# pnode.net
KiCad netlist of a schematic drawn in EAGLE
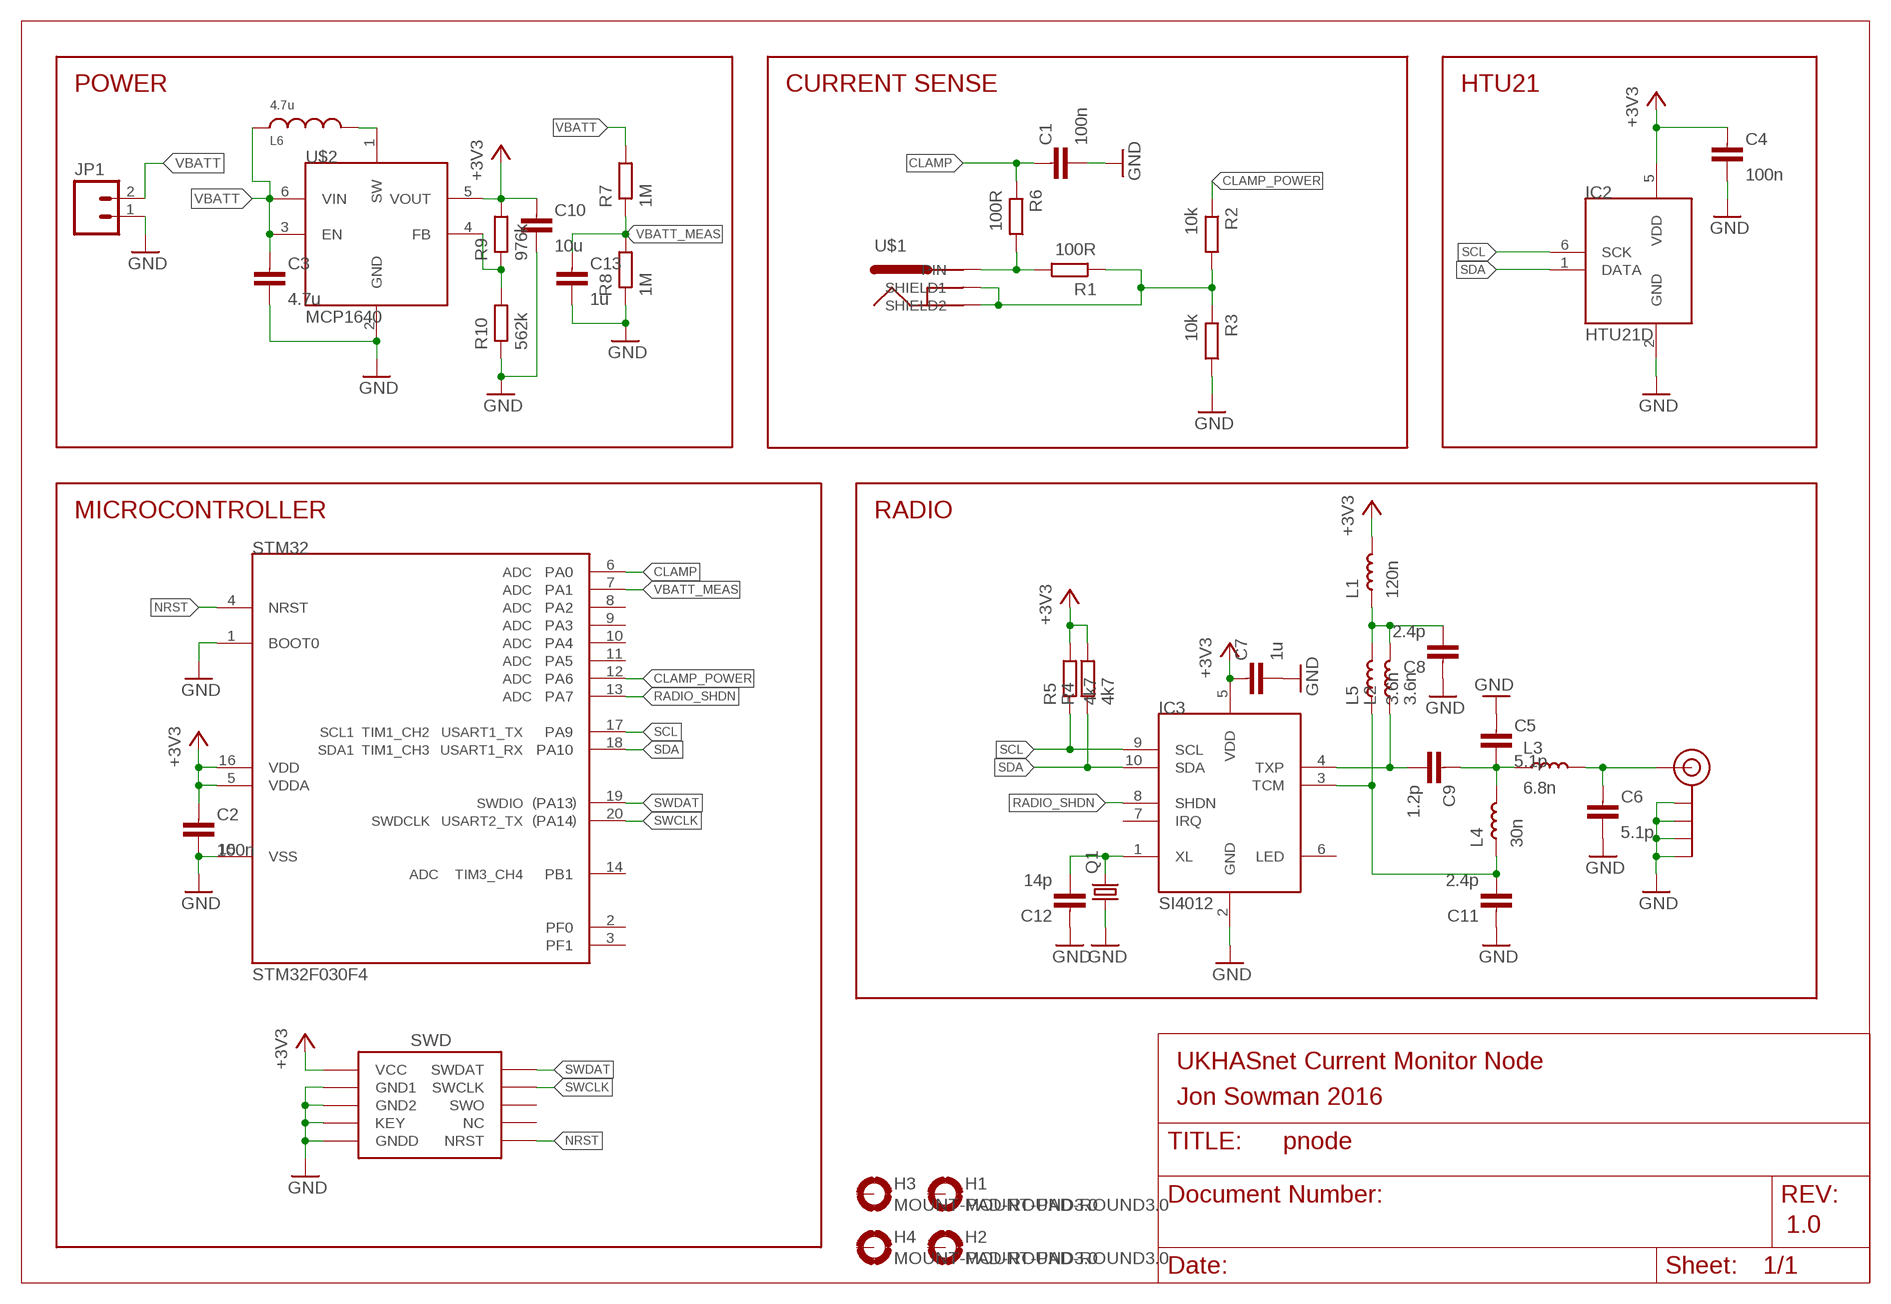
[diagram p0: schematic, sheet 1]

(export (version "E")
  (design (tool "Eeschema 10.0.6"))
  (components
    (comp (ref "C1")
      (value "100n")
      (footprint "eagle-import:C0603-N")
      (libsource (lib "eagle-import") (part "CAPACITOR0603-N"))
    )
    (comp (ref "C2")
      (value "100n")
      (footprint "eagle-import:C0603-N")
      (libsource (lib "eagle-import") (part "CAPACITOR0603-N"))
    )
    (comp (ref "C3")
      (value "4.7u")
      (footprint "eagle-import:C0603-N")
      (libsource (lib "eagle-import") (part "CAPACITOR0603-N"))
    )
    (comp (ref "C4")
      (value "100n")
      (footprint "eagle-import:C0603-N")
      (libsource (lib "eagle-import") (part "CAPACITOR0603-N"))
    )
    (comp (ref "C5")
      (value "5.1p")
      (footprint "eagle-import:C0603-N")
      (libsource (lib "eagle-import") (part "CAPACITOR0603-N"))
    )
    (comp (ref "C6")
      (value "5.1p")
      (footprint "eagle-import:C0603-N")
      (libsource (lib "eagle-import") (part "CAPACITOR0603-N"))
    )
    (comp (ref "C7")
      (value "1u")
      (footprint "eagle-import:C0603-N")
      (libsource (lib "eagle-import") (part "CAPACITOR0603-N"))
    )
    (comp (ref "C8")
      (value "2.4p")
      (footprint "eagle-import:C0603-N")
      (libsource (lib "eagle-import") (part "CAPACITOR0603-N"))
    )
    (comp (ref "C9")
      (value "1.2p")
      (footprint "eagle-import:C0603-N")
      (libsource (lib "eagle-import") (part "CAPACITOR0603-N"))
    )
    (comp (ref "C10")
      (value "10u")
      (footprint "eagle-import:C0603-N")
      (libsource (lib "eagle-import") (part "CAPACITOR0603-N"))
    )
    (comp (ref "C11")
      (value "2.4p")
      (footprint "eagle-import:C0603-N")
      (libsource (lib "eagle-import") (part "CAPACITOR0603-N"))
    )
    (comp (ref "C12")
      (value "14p")
      (footprint "eagle-import:C0603-N")
      (libsource (lib "eagle-import") (part "CAPACITOR0603-N"))
    )
    (comp (ref "C13")
      (value "1u")
      (footprint "eagle-import:C0603-N")
      (libsource (lib "eagle-import") (part "CAPACITOR0603-N"))
    )
    (comp (ref "H1")
      (value "MOUNT-PAD-ROUND3.0")
      (footprint "eagle-import:3,0-PAD")
      (libsource (lib "eagle-import") (part "MOUNT-PAD-ROUND3.0"))
    )
    (comp (ref "H2")
      (value "MOUNT-PAD-ROUND3.0")
      (footprint "eagle-import:3,0-PAD")
      (libsource (lib "eagle-import") (part "MOUNT-PAD-ROUND3.0"))
    )
    (comp (ref "H3")
      (value "MOUNT-PAD-ROUND3.0")
      (footprint "eagle-import:3,0-PAD")
      (libsource (lib "eagle-import") (part "MOUNT-PAD-ROUND3.0"))
    )
    (comp (ref "H4")
      (value "MOUNT-PAD-ROUND3.0")
      (footprint "eagle-import:3,0-PAD")
      (libsource (lib "eagle-import") (part "MOUNT-PAD-ROUND3.0"))
    )
    (comp (ref "IC2")
      (value "HTU21D")
      (footprint "eagle-import:DFN6-L")
      (libsource (lib "eagle-import") (part "HTU21D"))
    )
    (comp (ref "IC3")
      (value "SI4012")
      (footprint "eagle-import:MSOP10")
      (libsource (lib "eagle-import") (part "SI4012"))
    )
    (comp (ref "J$1")
      (value "SMA_EDGE")
      (footprint "eagle-import:SMA-EDGE")
      (libsource (lib "eagle-import") (part "SMA_EDGE"))
    )
    (comp (ref "J1")
      (value "SWD_SHROUD_SMD")
      (footprint "eagle-import:SWD_SMD_SHROUD")
      (libsource (lib "eagle-import") (part "SWD_SHROUD_SMD"))
    )
    (comp (ref "JP1")
      (value "M02PTH")
      (footprint "eagle-import:1X02")
      (libsource (lib "eagle-import") (part "M02PTH"))
    )
    (comp (ref "L1")
      (value "120n")
      (footprint "eagle-import:L0603-N")
      (libsource (lib "eagle-import") (part "INDUCTOR0603-N"))
    )
    (comp (ref "L2")
      (value "3.6n")
      (footprint "eagle-import:L0402-N")
      (libsource (lib "eagle-import") (part "INDUCTOR0402-N"))
    )
    (comp (ref "L3")
      (value "6.8n")
      (footprint "eagle-import:L0402-N")
      (libsource (lib "eagle-import") (part "INDUCTOR0402-N"))
    )
    (comp (ref "L4")
      (value "30n")
      (footprint "eagle-import:L0402-N")
      (libsource (lib "eagle-import") (part "INDUCTOR0402-N"))
    )
    (comp (ref "L5")
      (value "3.6n")
      (footprint "eagle-import:L0402-N")
      (libsource (lib "eagle-import") (part "INDUCTOR0402-N"))
    )
    (comp (ref "L6")
      (value "4.7u")
      (footprint "eagle-import:BOURNS_SDE0403A")
      (libsource (lib "eagle-import") (part "BOURNS_SDE0403A"))
    )
    (comp (ref "Q1")
      (value "CRYSTALHC49S")
      (footprint "eagle-import:HC49_S")
      (libsource (lib "eagle-import") (part "CRYSTALHC49S"))
    )
    (comp (ref "R1")
      (value "100R")
      (footprint "eagle-import:R0603-N")
      (libsource (lib "eagle-import") (part "RESISTOR0603-N"))
    )
    (comp (ref "R2")
      (value "10k")
      (footprint "eagle-import:R0603-N")
      (libsource (lib "eagle-import") (part "RESISTOR0603-N"))
    )
    (comp (ref "R3")
      (value "10k")
      (footprint "eagle-import:R0603-N")
      (libsource (lib "eagle-import") (part "RESISTOR0603-N"))
    )
    (comp (ref "R4")
      (value "4k7")
      (footprint "eagle-import:R0603-N")
      (libsource (lib "eagle-import") (part "RESISTOR0603-N"))
    )
    (comp (ref "R5")
      (value "4k7")
      (footprint "eagle-import:R0603-N")
      (libsource (lib "eagle-import") (part "RESISTOR0603-N"))
    )
    (comp (ref "R6")
      (value "100R")
      (footprint "eagle-import:R0603-N")
      (libsource (lib "eagle-import") (part "RESISTOR0603-N"))
    )
    (comp (ref "R7")
      (value "1M")
      (footprint "eagle-import:R0603-N")
      (libsource (lib "eagle-import") (part "RESISTOR0603-N"))
    )
    (comp (ref "R8")
      (value "1M")
      (footprint "eagle-import:R0603-N")
      (libsource (lib "eagle-import") (part "RESISTOR0603-N"))
    )
    (comp (ref "R9")
      (value "976k")
      (footprint "eagle-import:R0603-N")
      (libsource (lib "eagle-import") (part "RESISTOR0603-N"))
    )
    (comp (ref "R10")
      (value "562k")
      (footprint "eagle-import:R0603-N")
      (libsource (lib "eagle-import") (part "RESISTOR0603-N"))
    )
    (comp (ref "STM32")
      (value "STM32F030F4")
      (footprint "eagle-import:TSSOP20")
      (libsource (lib "eagle-import") (part "STM32F030F4"))
    )
    (comp (ref "U$1")
      (value "13MM_DC_JACKPTH")
      (footprint "eagle-import:13MM_DC_JACK")
      (libsource (lib "eagle-import") (part "13MM_DC_JACKPTH"))
    )
    (comp (ref "U$2")
      (value "MCP1640")
      (footprint "eagle-import:SOT23-6")
      (libsource (lib "eagle-import") (part "MCP1640"))
    )
  )
  (nets
    (net (code "1") (name "+3V3") (class "Default")
      (node (ref "C10") (pin "1") (pinfunction "1_1") (pintype "passive"))
      (node (ref "C2") (pin "1") (pinfunction "1_1") (pintype "passive"))
      (node (ref "C4") (pin "1") (pinfunction "1_1") (pintype "passive"))
      (node (ref "C7") (pin "1") (pinfunction "1_1") (pintype "passive"))
      (node (ref "IC2") (pin "5") (pinfunction "VDD_5") (pintype "power_in"))
      (node (ref "IC3") (pin "5") (pinfunction "VDD_5") (pintype "power_in"))
      (node (ref "J1") (pin "1") (pinfunction "VCC_1") (pintype "power_in"))
      (node (ref "L1") (pin "2") (pinfunction "P$2_2") (pintype "passive"))
      (node (ref "R4") (pin "2") (pinfunction "P$2_2") (pintype "passive"))
      (node (ref "R5") (pin "2") (pinfunction "P$2_2") (pintype "passive"))
      (node (ref "R9") (pin "2") (pinfunction "P$2_2") (pintype "passive"))
      (node (ref "STM32") (pin "16") (pinfunction "VDD_16") (pintype "power_in"))
      (node (ref "STM32") (pin "5") (pinfunction "VDDA_5") (pintype "power_in"))
      (node (ref "U$2") (pin "5") (pinfunction "VOUT_5") (pintype "output"))
    )
    (net (code "2") (name "CLAMP") (class "Default")
      (node (ref "C1") (pin "1") (pinfunction "1_1") (pintype "passive"))
      (node (ref "R6") (pin "1") (pinfunction "P$1_1") (pintype "passive"))
      (node (ref "STM32") (pin "6") (pinfunction "PA0_6") (pintype "bidirectional"))
    )
    (net (code "3") (name "CLAMP_POWER") (class "Default")
      (node (ref "R2") (pin "1") (pinfunction "P$1_1") (pintype "passive"))
      (node (ref "STM32") (pin "12") (pinfunction "PA6_12") (pintype "bidirectional"))
    )
    (net (code "4") (name "GND") (class "Default")
      (node (ref "C1") (pin "2") (pinfunction "2_2") (pintype "passive"))
      (node (ref "C10") (pin "2") (pinfunction "2_2") (pintype "passive"))
      (node (ref "C11") (pin "1") (pinfunction "1_1") (pintype "passive"))
      (node (ref "C12") (pin "1") (pinfunction "1_1") (pintype "passive"))
      (node (ref "C13") (pin "2") (pinfunction "2_2") (pintype "passive"))
      (node (ref "C2") (pin "2") (pinfunction "2_2") (pintype "passive"))
      (node (ref "C3") (pin "2") (pinfunction "2_2") (pintype "passive"))
      (node (ref "C4") (pin "2") (pinfunction "2_2") (pintype "passive"))
      (node (ref "C5") (pin "1") (pinfunction "1_1") (pintype "passive"))
      (node (ref "C6") (pin "2") (pinfunction "2_2") (pintype "passive"))
      (node (ref "C7") (pin "2") (pinfunction "2_2") (pintype "passive"))
      (node (ref "C8") (pin "1") (pinfunction "1_1") (pintype "passive"))
      (node (ref "IC2") (pin "2") (pinfunction "GND_2") (pintype "power_in"))
      (node (ref "IC3") (pin "2") (pinfunction "GND_2") (pintype "power_in"))
      (node (ref "J$1") (pin "GND@0") (pinfunction "GND_GND@0") (pintype "bidirectional"))
      (node (ref "J$1") (pin "GND@1") (pinfunction "GND_GND@1") (pintype "bidirectional"))
      (node (ref "J$1") (pin "GND@2") (pinfunction "GND_GND@2") (pintype "bidirectional"))
      (node (ref "J$1") (pin "GND@3") (pinfunction "GND_GND@3") (pintype "bidirectional"))
      (node (ref "J1") (pin "3") (pinfunction "GND1_3") (pintype "power_in"))
      (node (ref "J1") (pin "5") (pinfunction "GND2_5") (pintype "power_in"))
      (node (ref "J1") (pin "7") (pinfunction "KEY_7") (pintype "bidirectional"))
      (node (ref "J1") (pin "9") (pinfunction "GNDD_9") (pintype "power_in"))
      (node (ref "JP1") (pin "1") (pinfunction "1_1") (pintype "passive"))
      (node (ref "Q1") (pin "1") (pinfunction "1_1") (pintype "passive"))
      (node (ref "R10") (pin "1") (pinfunction "P$1_1") (pintype "passive"))
      (node (ref "R3") (pin "2") (pinfunction "P$2_2") (pintype "passive"))
      (node (ref "R8") (pin "1") (pinfunction "P$1_1") (pintype "passive"))
      (node (ref "STM32") (pin "1") (pinfunction "BOOT0_1") (pintype "input"))
      (node (ref "STM32") (pin "15") (pinfunction "VSS_15") (pintype "power_in"))
      (node (ref "U$2") (pin "2") (pinfunction "GND_2") (pintype "power_in"))
    )
    (net (code "5") (name "NRST") (class "Default")
      (node (ref "J1") (pin "10") (pinfunction "NRST_10") (pintype "bidirectional"))
      (node (ref "STM32") (pin "4") (pinfunction "NRST_4") (pintype "input"))
    )
    (net (code "6") (name "Net-(IC3-TCM)") (class "Default")
      (node (ref "C11") (pin "2") (pinfunction "2_2") (pintype "passive"))
      (node (ref "IC3") (pin "3") (pinfunction "TCM_3") (pintype "output"))
      (node (ref "L4") (pin "1") (pinfunction "P$1_1") (pintype "passive"))
      (node (ref "L5") (pin "1") (pinfunction "P$1_1") (pintype "passive"))
    )
    (net (code "7") (name "Net-(IC3-TXP)") (class "Default")
      (node (ref "C9") (pin "2") (pinfunction "2_2") (pintype "passive"))
      (node (ref "IC3") (pin "4") (pinfunction "TXP_4") (pintype "output"))
      (node (ref "L2") (pin "1") (pinfunction "P$1_1") (pintype "passive"))
    )
    (net (code "8") (name "Net-(IC3-XL)") (class "Default")
      (node (ref "C12") (pin "2") (pinfunction "2_2") (pintype "passive"))
      (node (ref "IC3") (pin "1") (pinfunction "XL_1") (pintype "bidirectional"))
      (node (ref "Q1") (pin "2") (pinfunction "2_2") (pintype "passive"))
    )
    (net (code "9") (name "Net-(J$1-SIGNAL)") (class "Default")
      (node (ref "C6") (pin "1") (pinfunction "1_1") (pintype "passive"))
      (node (ref "J$1") (pin "SIG") (pinfunction "SIGNAL_SIG") (pintype "bidirectional"))
      (node (ref "L3") (pin "2") (pinfunction "P$2_2") (pintype "passive"))
    )
    (net (code "10") (name "Net-(L1-P$1)") (class "Default")
      (node (ref "C8") (pin "2") (pinfunction "2_2") (pintype "passive"))
      (node (ref "L1") (pin "1") (pinfunction "P$1_1") (pintype "passive"))
      (node (ref "L2") (pin "2") (pinfunction "P$2_2") (pintype "passive"))
      (node (ref "L5") (pin "2") (pinfunction "P$2_2") (pintype "passive"))
    )
    (net (code "11") (name "Net-(L3-P$1)") (class "Default")
      (node (ref "C5") (pin "2") (pinfunction "2_2") (pintype "passive"))
      (node (ref "C9") (pin "1") (pinfunction "1_1") (pintype "passive"))
      (node (ref "L3") (pin "1") (pinfunction "P$1_1") (pintype "passive"))
      (node (ref "L4") (pin "2") (pinfunction "P$2_2") (pintype "passive"))
    )
    (net (code "12") (name "Net-(R1-P$1)") (class "Default")
      (node (ref "R1") (pin "1") (pinfunction "P$1_1") (pintype "passive"))
      (node (ref "R2") (pin "2") (pinfunction "P$2_2") (pintype "passive"))
      (node (ref "R3") (pin "1") (pinfunction "P$1_1") (pintype "passive"))
      (node (ref "U$1") (pin "2") (pinfunction "SHIELD1_2") (pintype "bidirectional"))
      (node (ref "U$1") (pin "3") (pinfunction "SHIELD2_3") (pintype "bidirectional"))
    )
    (net (code "13") (name "Net-(R1-P$2)") (class "Default")
      (node (ref "R1") (pin "2") (pinfunction "P$2_2") (pintype "passive"))
      (node (ref "R6") (pin "2") (pinfunction "P$2_2") (pintype "passive"))
      (node (ref "U$1") (pin "1") (pinfunction "PIN_1") (pintype "bidirectional"))
    )
    (net (code "14") (name "Net-(R10-P$2)") (class "Default")
      (node (ref "R10") (pin "2") (pinfunction "P$2_2") (pintype "passive"))
      (node (ref "R9") (pin "1") (pinfunction "P$1_1") (pintype "passive"))
      (node (ref "U$2") (pin "4") (pinfunction "FB_4") (pintype "input"))
    )
    (net (code "15") (name "Net-(U$2-SW)") (class "Default")
      (node (ref "L6") (pin "P$2") (pinfunction "P$2_P$2") (pintype "bidirectional"))
      (node (ref "U$2") (pin "1") (pinfunction "SW_1") (pintype "input"))
    )
    (net (code "16") (name "RADIO_SHDN") (class "Default")
      (node (ref "IC3") (pin "8") (pinfunction "SHDN_8") (pintype "input"))
      (node (ref "STM32") (pin "13") (pinfunction "PA7_13") (pintype "bidirectional"))
    )
    (net (code "17") (name "SCL") (class "Default")
      (node (ref "IC2") (pin "6") (pinfunction "SCK_6") (pintype "input"))
      (node (ref "IC3") (pin "9") (pinfunction "SCL_9") (pintype "input"))
      (node (ref "R5") (pin "1") (pinfunction "P$1_1") (pintype "passive"))
      (node (ref "STM32") (pin "17") (pinfunction "PA9_17") (pintype "bidirectional"))
    )
    (net (code "18") (name "SDA") (class "Default")
      (node (ref "IC2") (pin "1") (pinfunction "DATA_1") (pintype "bidirectional"))
      (node (ref "IC3") (pin "10") (pinfunction "SDA_10") (pintype "bidirectional"))
      (node (ref "R4") (pin "1") (pinfunction "P$1_1") (pintype "passive"))
      (node (ref "STM32") (pin "18") (pinfunction "PA10_18") (pintype "bidirectional"))
    )
    (net (code "19") (name "SWCLK") (class "Default")
      (node (ref "J1") (pin "4") (pinfunction "SWCLK_4") (pintype "bidirectional"))
      (node (ref "STM32") (pin "20") (pinfunction "PA14_20") (pintype "bidirectional"))
    )
    (net (code "20") (name "SWDAT") (class "Default")
      (node (ref "J1") (pin "2") (pinfunction "SWDAT_2") (pintype "bidirectional"))
      (node (ref "STM32") (pin "19") (pinfunction "PA13_19") (pintype "bidirectional"))
    )
    (net (code "21") (name "VBATT") (class "Default")
      (node (ref "C3") (pin "1") (pinfunction "1_1") (pintype "passive"))
      (node (ref "JP1") (pin "2") (pinfunction "2_2") (pintype "passive"))
      (node (ref "L6") (pin "P$1") (pinfunction "P$1_P$1") (pintype "bidirectional"))
      (node (ref "R7") (pin "2") (pinfunction "P$2_2") (pintype "passive"))
      (node (ref "U$2") (pin "3") (pinfunction "EN_3") (pintype "input"))
      (node (ref "U$2") (pin "6") (pinfunction "VIN_6") (pintype "power_in"))
    )
    (net (code "22") (name "VBATT_MEAS") (class "Default")
      (node (ref "C13") (pin "1") (pinfunction "1_1") (pintype "passive"))
      (node (ref "R7") (pin "1") (pinfunction "P$1_1") (pintype "passive"))
      (node (ref "R8") (pin "2") (pinfunction "P$2_2") (pintype "passive"))
      (node (ref "STM32") (pin "7") (pinfunction "PA1_7") (pintype "bidirectional"))
    )
    (net (code "23") (name "unconnected-(H1-MOUNT-PadB3,0)") (class "Default")
      (node (ref "H1") (pin "B3,0") (pinfunction "MOUNT_B3,0") (pintype "passive"))
    )
    (net (code "24") (name "unconnected-(H2-MOUNT-PadB3,0)") (class "Default")
      (node (ref "H2") (pin "B3,0") (pinfunction "MOUNT_B3,0") (pintype "passive"))
    )
    (net (code "25") (name "unconnected-(H3-MOUNT-PadB3,0)") (class "Default")
      (node (ref "H3") (pin "B3,0") (pinfunction "MOUNT_B3,0") (pintype "passive"))
    )
    (net (code "26") (name "unconnected-(H4-MOUNT-PadB3,0)") (class "Default")
      (node (ref "H4") (pin "B3,0") (pinfunction "MOUNT_B3,0") (pintype "passive"))
    )
    (net (code "27") (name "unconnected-(IC3-IRQ-Pad7)") (class "Default")
      (node (ref "IC3") (pin "7") (pinfunction "IRQ_7") (pintype "output"))
    )
    (net (code "28") (name "unconnected-(IC3-LED-Pad6)") (class "Default")
      (node (ref "IC3") (pin "6") (pinfunction "LED_6") (pintype "output"))
    )
    (net (code "29") (name "unconnected-(J1-NC-Pad8)") (class "Default")
      (node (ref "J1") (pin "8") (pinfunction "NC_8") (pintype "no_connect"))
    )
    (net (code "30") (name "unconnected-(J1-SWO-Pad6)") (class "Default")
      (node (ref "J1") (pin "6") (pinfunction "SWO_6") (pintype "bidirectional"))
    )
    (net (code "31") (name "unconnected-(STM32-PA2-Pad8)") (class "Default")
      (node (ref "STM32") (pin "8") (pinfunction "PA2_8") (pintype "bidirectional"))
    )
    (net (code "32") (name "unconnected-(STM32-PA3-Pad9)") (class "Default")
      (node (ref "STM32") (pin "9") (pinfunction "PA3_9") (pintype "bidirectional"))
    )
    (net (code "33") (name "unconnected-(STM32-PA4-Pad10)") (class "Default")
      (node (ref "STM32") (pin "10") (pinfunction "PA4_10") (pintype "bidirectional"))
    )
    (net (code "34") (name "unconnected-(STM32-PA5-Pad11)") (class "Default")
      (node (ref "STM32") (pin "11") (pinfunction "PA5_11") (pintype "bidirectional"))
    )
    (net (code "35") (name "unconnected-(STM32-PB1-Pad14)") (class "Default")
      (node (ref "STM32") (pin "14") (pinfunction "PB1_14") (pintype "bidirectional"))
    )
    (net (code "36") (name "unconnected-(STM32-PF0-Pad2)") (class "Default")
      (node (ref "STM32") (pin "2") (pinfunction "PF0_2") (pintype "bidirectional"))
    )
    (net (code "37") (name "unconnected-(STM32-PF1-Pad3)") (class "Default")
      (node (ref "STM32") (pin "3") (pinfunction "PF1_3") (pintype "bidirectional"))
    )
  )
)
